# H1AR20.net
KiCad netlist of a schematic drawn in EAGLE
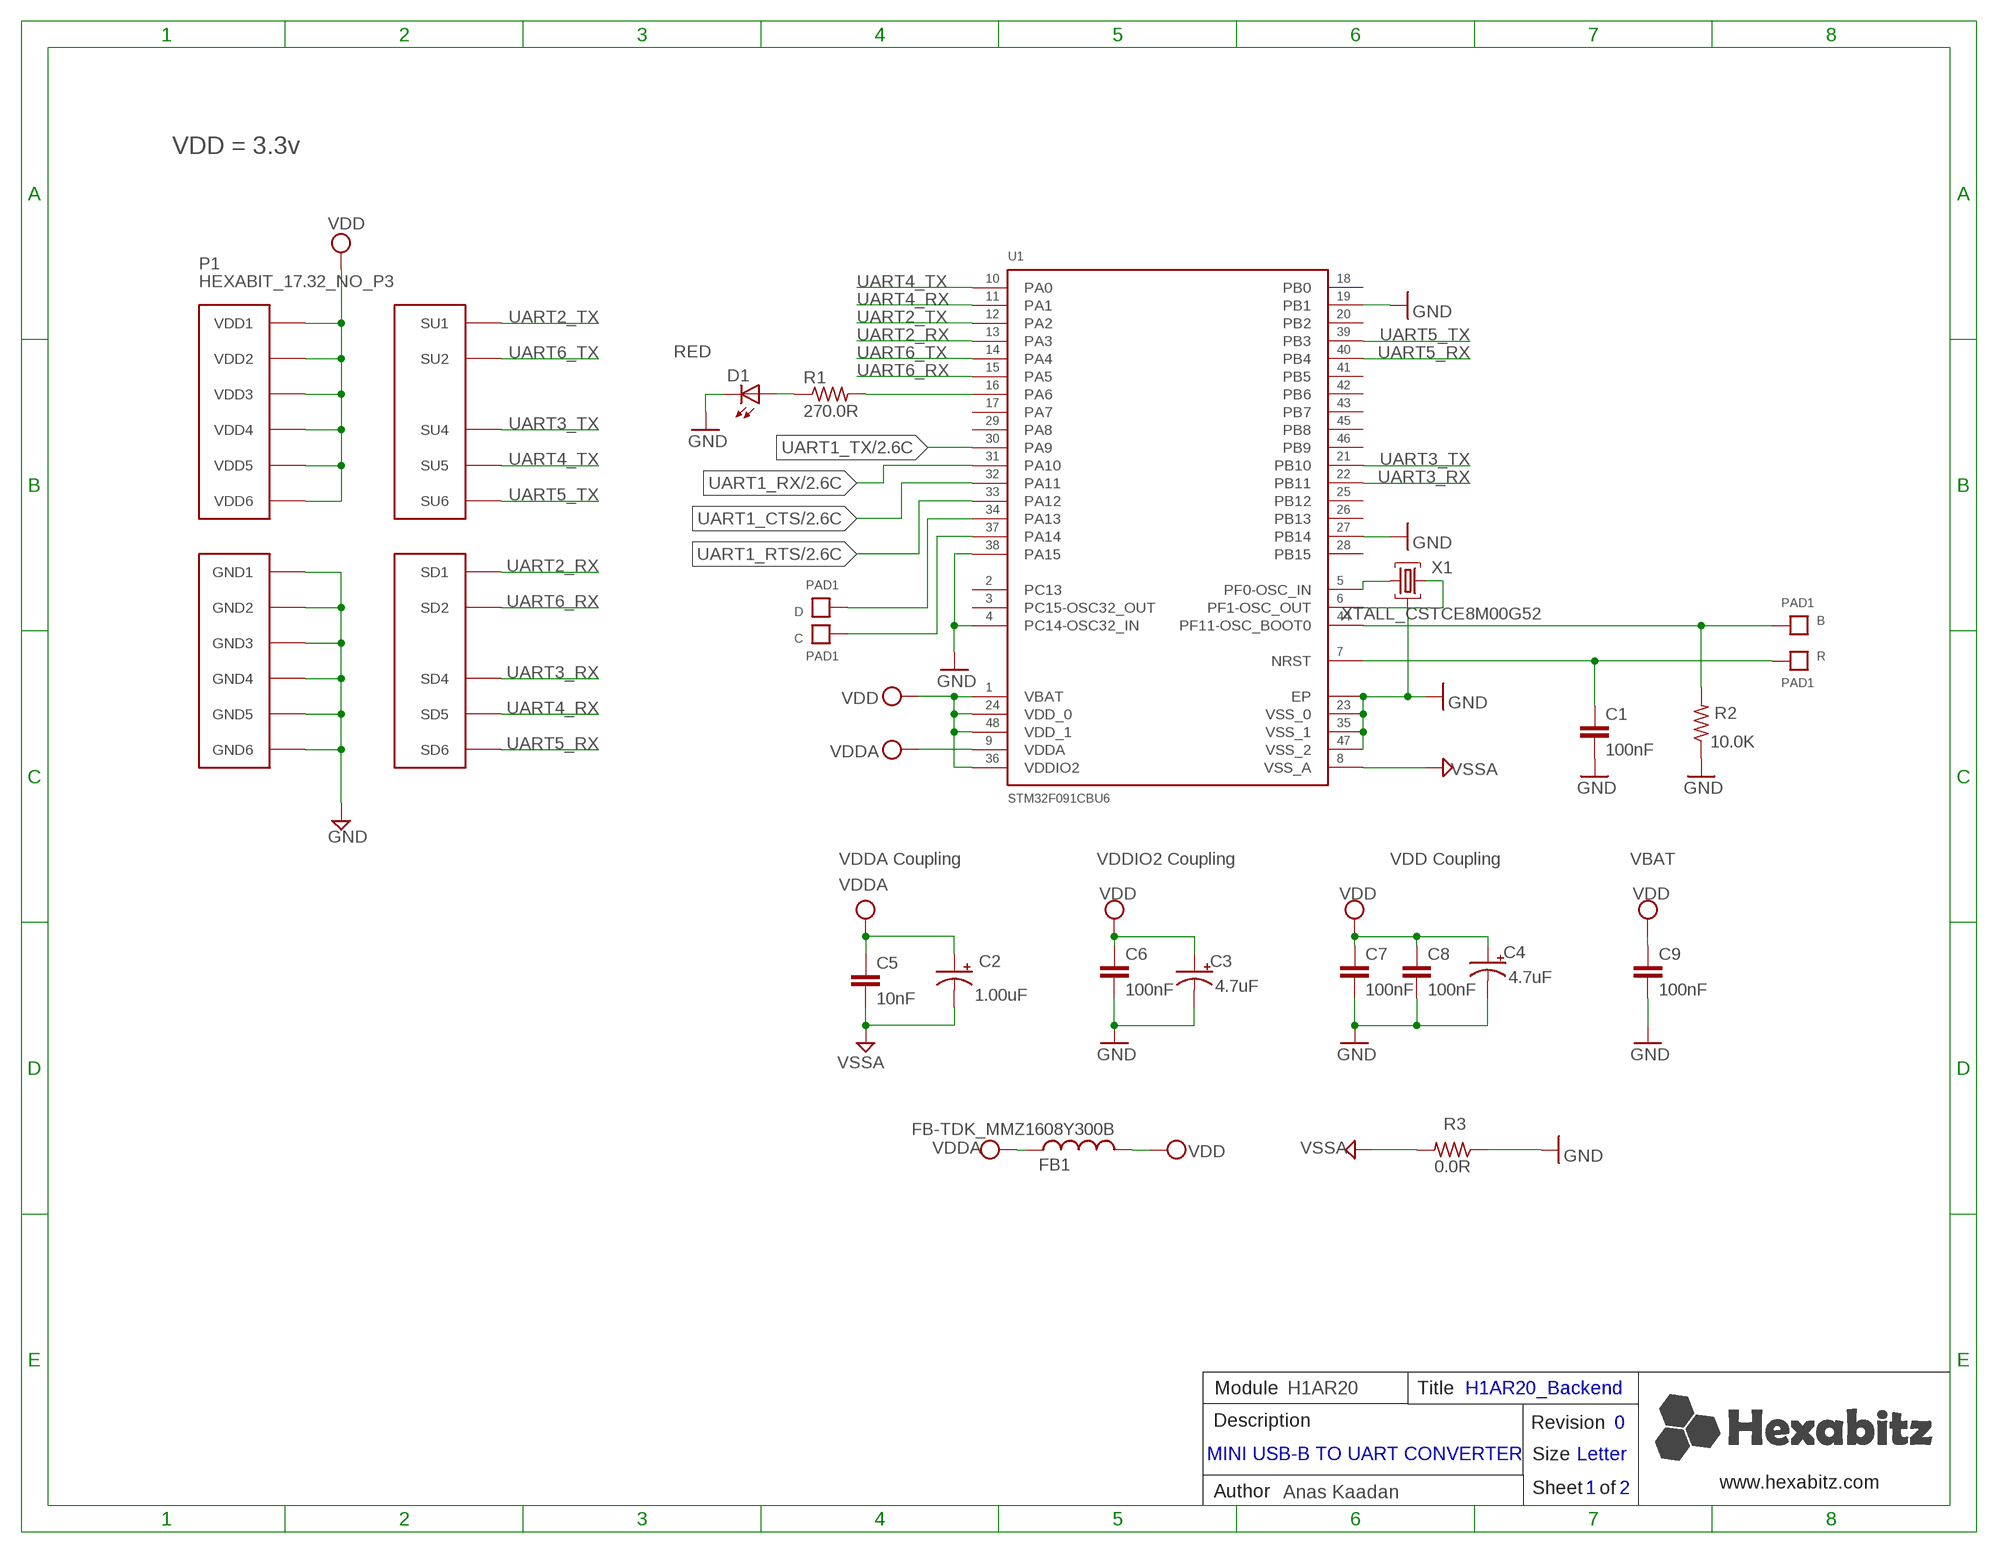
[diagram p0: schematic, sheet 1]
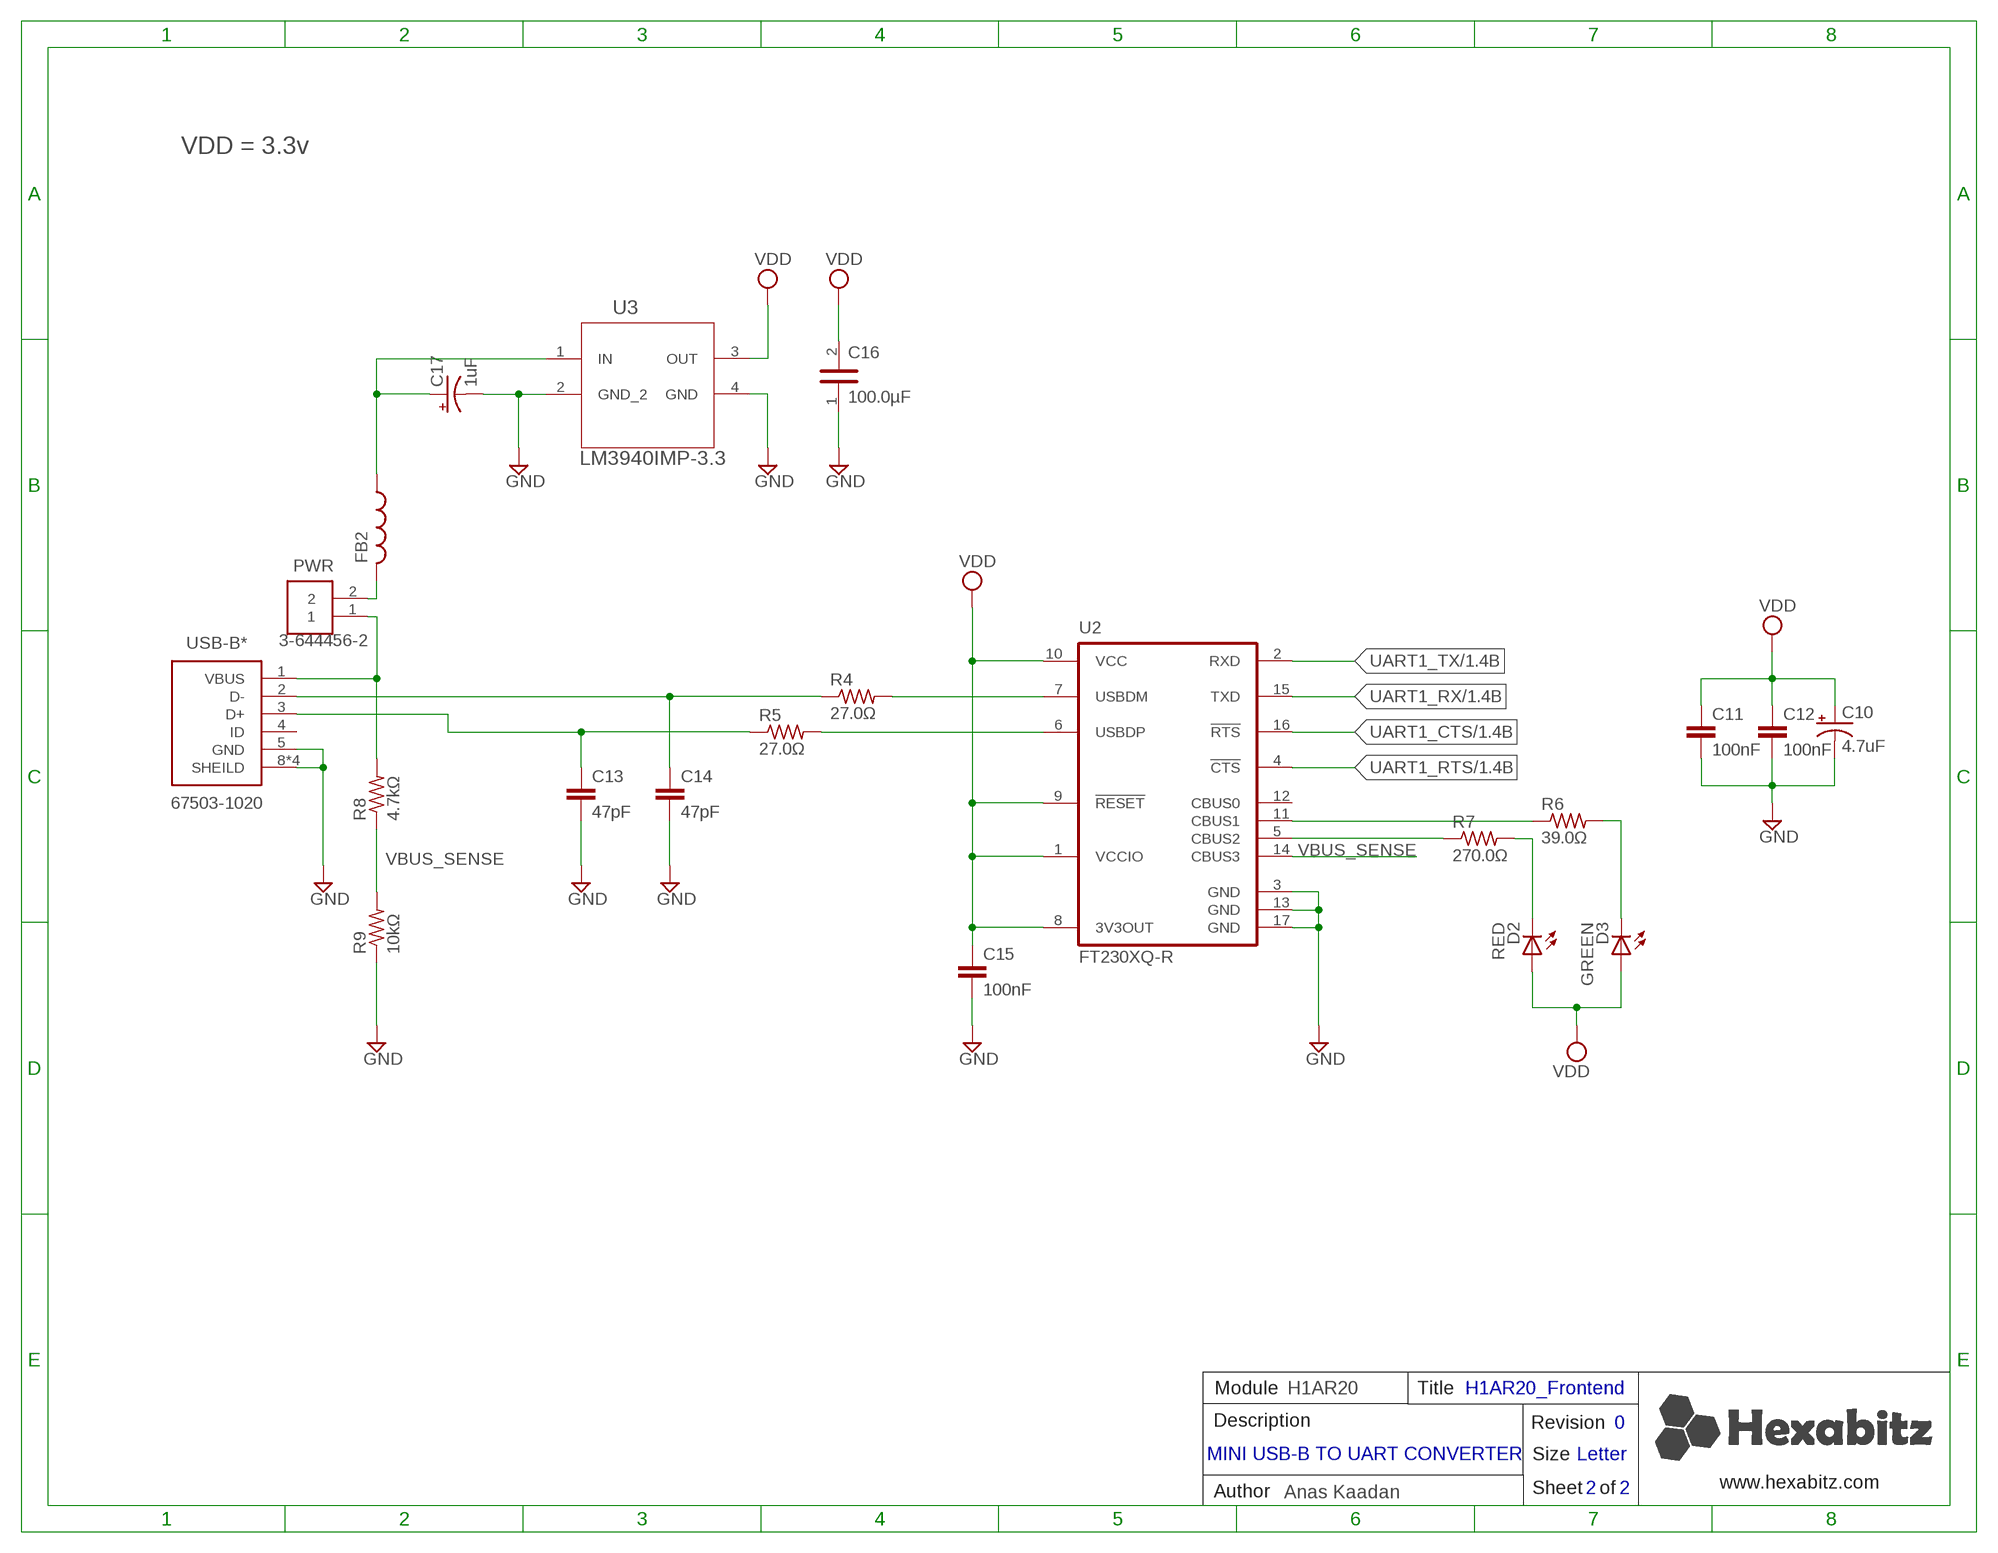
[diagram p1: schematic, sheet 2]

(export (version "E")
  (design (tool "Eeschema 10.0.6"))
  (components
    (comp (ref "B")
      (value "PAD1")
      (footprint "eagle-import:PAD1")
      (libsource (lib "eagle-import") (part "PAD1"))
    )
    (comp (ref "C")
      (value "PAD1")
      (footprint "eagle-import:PAD1")
      (libsource (lib "eagle-import") (part "PAD1"))
    )
    (comp (ref "C1")
      (value "100nF")
      (footprint "eagle-import:C-0603")
      (fields
        (field (name "CAPACITANCE") "100nF")
        (field (name "MFN") "KEMET")
        (field (name "MPN") "C0603C104K8RACTU")
        (field (name "OCTOPART_URL") "https://octopart.com/c0603c104k8ractu-kemet-145075?r=sp&s=9bS9ASSwSEqMCE9KBEQZ0g")
        (field (name "TOLERANCE") "10%")
        (field (name "VOLTAGE_RATING") "10V")
      )
      (libsource (lib "eagle-import") (part "C-0603"))
    )
    (comp (ref "C2")
      (value "1.00uF")
      (footprint "eagle-import:C-0805-POL")
      (fields
        (field (name "CAPACITANCE") "1.00uF")
        (field (name "MFN") "Yageo")
        (field (name "MPN") "CC0805KKX7R7BB105")
        (field (name "OCTOPART_URL") "https://octopart.com/cc0805kkx7r7bb105-yageo-8376555?r=sp&s=YKl1wwtkROau_X5nniH2ig")
        (field (name "TOLERANCE") "10%")
        (field (name "VOLTAGE_RATING") "16V")
      )
      (libsource (lib "eagle-import") (part "C-0805-POL"))
    )
    (comp (ref "C3")
      (value "4.7uF")
      (footprint "eagle-import:C-0805-POL")
      (fields
        (field (name "CAPACITANCE") "4.7uF")
        (field (name "MFN") "Murata")
        (field (name "MPN") "GRM21BC81E475KA12L")
        (field (name "OCTOPART_URL") "https://octopart.com/grm21bc81e475ka12l-murata-10331911?r=sp&s=RY3qZSD8T6mG6TC9CHI5qQ")
        (field (name "TOLERANCE") "10%")
        (field (name "VOLTAGE_RATING") "25V")
      )
      (libsource (lib "eagle-import") (part "C-0805-POL"))
    )
    (comp (ref "C4")
      (value "4.7uF")
      (footprint "eagle-import:C-0805-POL")
      (fields
        (field (name "CAPACITANCE") "4.7uF")
        (field (name "MFN") "Murata")
        (field (name "MPN") "GRM21BC81E475KA12L")
        (field (name "OCTOPART_URL") "https://octopart.com/grm21bc81e475ka12l-murata-10331911?r=sp&s=RY3qZSD8T6mG6TC9CHI5qQ")
        (field (name "TOLERANCE") "10%")
        (field (name "VOLTAGE_RATING") "25V")
      )
      (libsource (lib "eagle-import") (part "C-0805-POL"))
    )
    (comp (ref "C5")
      (value "10nF")
      (footprint "eagle-import:C-0603")
      (fields
        (field (name "CAPACITANCE") "10nF")
        (field (name "MFN") "KEMET")
        (field (name "MPN") "C0603C103K5RACTU")
        (field (name "OCTOPART_URL") "https://octopart.com/c0603c103k5ractu-kemet-133094?r=sp&s=R_iPBxLnSmGqhkU2rIMFpg")
        (field (name "TOLERANCE") "10%")
        (field (name "VOLTAGE_RATING") "50V")
      )
      (libsource (lib "eagle-import") (part "C-0603"))
    )
    (comp (ref "C6")
      (value "100nF")
      (footprint "eagle-import:C-0603")
      (fields
        (field (name "CAPACITANCE") "100nF")
        (field (name "MFN") "KEMET")
        (field (name "MPN") "C0603C104K8RACTU")
        (field (name "OCTOPART_URL") "https://octopart.com/c0603c104k8ractu-kemet-145075?r=sp&s=9bS9ASSwSEqMCE9KBEQZ0g")
        (field (name "TOLERANCE") "10%")
        (field (name "VOLTAGE_RATING") "10V")
      )
      (libsource (lib "eagle-import") (part "C-0603"))
    )
    (comp (ref "C7")
      (value "100nF")
      (footprint "eagle-import:C-0603")
      (fields
        (field (name "CAPACITANCE") "100nF")
        (field (name "MFN") "KEMET")
        (field (name "MPN") "C0603C104K8RACTU")
        (field (name "OCTOPART_URL") "https://octopart.com/c0603c104k8ractu-kemet-145075?r=sp&s=9bS9ASSwSEqMCE9KBEQZ0g")
        (field (name "TOLERANCE") "10%")
        (field (name "VOLTAGE_RATING") "10")
      )
      (libsource (lib "eagle-import") (part "C-0603"))
    )
    (comp (ref "C8")
      (value "100nF")
      (footprint "eagle-import:C-0603")
      (fields
        (field (name "CAPACITANCE") "100nF")
        (field (name "MFN") "KEMET")
        (field (name "MPN") "C0603C104K8RACTU")
        (field (name "OCTOPART_URL") "https://octopart.com/c0603c104k8ractu-kemet-145075?r=sp&s=9bS9ASSwSEqMCE9KBEQZ0g")
        (field (name "TOLERANCE") "10%")
        (field (name "VOLTAGE_RATING") "10V")
      )
      (libsource (lib "eagle-import") (part "C-0603"))
    )
    (comp (ref "C9")
      (value "100nF")
      (footprint "eagle-import:C-0603")
      (fields
        (field (name "CAPACITANCE") "100nF")
        (field (name "MFN") "KEMET")
        (field (name "MPN") "C0603C104K8RACTU")
        (field (name "OCTOPART_URL") "https://octopart.com/c0603c104k8ractu-kemet-145075?r=sp&s=9bS9ASSwSEqMCE9KBEQZ0g")
        (field (name "TOLERANCE") "10V")
        (field (name "VOLTAGE_RATING") "10%")
      )
      (libsource (lib "eagle-import") (part "C-0603"))
    )
    (comp (ref "D")
      (value "PAD1")
      (footprint "eagle-import:PAD1")
      (libsource (lib "eagle-import") (part "PAD1"))
    )
    (comp (ref "D1")
      (value "RED")
      (footprint "eagle-import:VLMS1300-GS08")
      (fields
        (field (name "MPN") "VLMS1300-GS08")
        (field (name "MFN") "Vishay")
        (field (name "MPN_1") "VLMS1300-GS08")
        (field (name "OCTOPART_URL") "https://octopart.com/vlms1300-gs08-vishay-21709201?r=sp&s=_gcP4_q8T1SC6PJQPTQ9yA")
      )
      (libsource (lib "eagle-import") (part "VLMS1300-GS08"))
    )
    (comp (ref "FB1")
      (value "FB-TDK_MMZ1608Y300B")
      (footprint "eagle-import:FB-TDK_MMZ1608Y300B")
      (fields
        (field (name "MFN") "TDK ")
        (field (name "MPN") "MMZ1608Y300B")
        (field (name "OCTOPART_URL") "https://octopart.com/mmz1608y300b-tdk-368280?r=sp&s=cd9_2ZEqQ9q9UNBuQgHAiA")
      )
      (libsource (lib "eagle-import") (part "FB-TDK_MMZ1608Y300B"))
    )
    (comp (ref "P1")
      (value "HEXABIT_17.32_NO_P3")
      (footprint "eagle-import:HEXABIT_17.32_NO_P3")
      (libsource (lib "eagle-import") (part "HEXABIT_?_NO_P317.32"))
    )
    (comp (ref "R")
      (value "PAD1")
      (footprint "eagle-import:PAD1")
      (libsource (lib "eagle-import") (part "PAD1"))
    )
    (comp (ref "R1")
      (value "270.0R")
      (footprint "eagle-import:R-0603")
      (fields
        (field (name "MFN") "Yageo")
        (field (name "MPN") "RC0603FR-07270RL")
        (field (name "OCTOPART_URL") "https://octopart.com/search?q=RC0603FR-07270RL&start=0")
        (field (name "RESISTANCE") "270.0 Ohm")
        (field (name "TOLERANCE") "1%")
      )
      (libsource (lib "eagle-import") (part "R-0603"))
    )
    (comp (ref "R2")
      (value "10.0K")
      (footprint "eagle-import:R-0603")
      (fields
        (field (name "MFN") "Vishay")
        (field (name "MPN") "CRCW060310K0JNEB")
        (field (name "OCTOPART_URL") "https://octopart.com/crcw060310k0jneb-vishay+dale-46603268")
        (field (name "RESISTANCE") "10.0K Ohm")
        (field (name "TOLERANCE") "5%")
      )
      (libsource (lib "eagle-import") (part "R-0603"))
    )
    (comp (ref "R3")
      (value "0.0R")
      (footprint "eagle-import:R-0603")
      (fields
        (field (name "MFN") "Yageo")
        (field (name "MPN") "RC0603JR-070RL")
        (field (name "OCTOPART_URL") "https://octopart.com/rc0603jr-070rl-yageo-1241539?r=sp&s=X2NteqRjRNWrnx42Y0aliA")
        (field (name "RESISTANCE") "0.0 Ohm")
      )
      (libsource (lib "eagle-import") (part "R-0603"))
    )
    (comp (ref "U1")
      (value "STM32F091CBU6")
      (footprint "eagle-import:STM32F091CBU6")
      (libsource (lib "eagle-import") (part "STM32F091CBU6"))
    )
    (comp (ref "X1")
      (value "XTALL_CSTCE8M00G52")
      (footprint "eagle-import:XTALL_CSTCE8M00G52")
      (fields (field (name "MPN") "CSTCE8M00G52Z-R0"))
      (libsource (lib "eagle-import") (part "XTALL_CSTCE8M00G52"))
    )
    (comp (ref "C10")
      (value "4.7uF")
      (footprint "eagle-import:C-0805-POL")
      (fields
        (field (name "CAPACITANCE") "4.7 µF")
        (field (name "MFN") "Panasonic")
        (field (name "MPN") "10TPU4R7MSI")
        (field (name "OCTOPART_URL") "https://octopart.com/10tpu4r7msi-panasonic-29487748")
        (field (name "TOLERANCE") "±20%")
        (field (name "VOLTAGE_RATING") "10.0 V")
      )
      (libsource (lib "eagle-import") (part "C-0805-POL"))
    )
    (comp (ref "C11")
      (value "100nF")
      (footprint "eagle-import:C-0603")
      (fields
        (field (name "CAPACITANCE") "100 nF")
        (field (name "MFN") "AVX")
        (field (name "MPN") "0603YC104K4T2A")
        (field (name "OCTOPART_URL") "https://octopart.com/0603yc104k4t2a-avx+interconnect+%2F+elco-8120651")
        (field (name "TOLERANCE") "±10%")
        (field (name "VOLTAGE_RATING") "16.0 V")
      )
      (libsource (lib "eagle-import") (part "C-0603"))
    )
    (comp (ref "C12")
      (value "100nF")
      (footprint "eagle-import:C-0603")
      (fields
        (field (name "CAPACITANCE") "100 nF")
        (field (name "MFN") "AVX")
        (field (name "MPN") "0603YC104K4T2A")
        (field (name "OCTOPART_URL") "https://octopart.com/0603yc104k4t2a-avx+interconnect+%2F+elco-8120651")
        (field (name "TOLERANCE") "±10%")
        (field (name "VOLTAGE_RATING") "16.0 V")
      )
      (libsource (lib "eagle-import") (part "C-0603"))
    )
    (comp (ref "C13")
      (value "47pF")
      (footprint "eagle-import:C-0603")
      (fields
        (field (name "CAPACITANCE") "47 pF")
        (field (name "MFN") "AVX")
        (field (name "MPN") "06035A470JAT2A")
        (field (name "OCTOPART_URL") "https://octopart.com/c3225x5r0j107m250ac-tdk-25947844?r=spc#")
        (field (name "TOLERANCE") "±5%")
        (field (name "VOLTAGE_RATING") "50.0 V")
      )
      (libsource (lib "eagle-import") (part "C-0603"))
    )
    (comp (ref "C14")
      (value "47pF")
      (footprint "eagle-import:C-0603")
      (fields
        (field (name "CAPACITANCE") "47 pF")
        (field (name "MFN") "AVX")
        (field (name "MPN") "06035A470JAT2A")
        (field (name "OCTOPART_URL") "https://octopart.com/06035a470jat2a-avx+interconnect+%2F+elco-46507018")
        (field (name "TOLERANCE") "±5%")
        (field (name "VOLTAGE_RATING") "50.0 V")
      )
      (libsource (lib "eagle-import") (part "C-0603"))
    )
    (comp (ref "C15")
      (value "100nF")
      (footprint "eagle-import:C-0603")
      (fields
        (field (name "CAPACITANCE") "100 nF")
        (field (name "MFN") "AVX")
        (field (name "MPN") "0603YC104K4T2A")
        (field (name "OCTOPART_URL") "https://octopart.com/0603yc104k4t2a-avx+interconnect+%2F+elco-8120651")
        (field (name "TOLERANCE") "±10%")
        (field (name "VOLTAGE_RATING") "16.0 V")
      )
      (libsource (lib "eagle-import") (part "C-0603"))
    )
    (comp (ref "C16")
      (value "100uF")
      (footprint "eagle-import:C-3225")
      (fields
        (field (name "CAPACITANCE") "100.0µF")
        (field (name "MPN") "C3225X5R0J107M250AC")
        (field (name "VOLTAGE") "6.3V")
      )
      (libsource (lib "eagle-import") (part "C-3225TDK_C3225X5R0J107M250AC_0_0"))
    )
    (comp (ref "C17")
      (value "1uF")
      (footprint "eagle-import:C-0805-POL")
      (fields
        (field (name "CAPACITANCE") "1.00 µF")
        (field (name "MFN") "AVX")
        (field (name "MPN") "TAJR105M016RNJ")
        (field (name "OCTOPART_URL") "http://octopart.com/tajr105m016rnj-avx-1188552")
        (field (name "TOLERANCE") "±20%")
        (field (name "VOLTAGE_RATING") "16.0 V")
      )
      (libsource (lib "eagle-import") (part "C-0805-POL"))
    )
    (comp (ref "D2")
      (value "RED")
      (footprint "eagle-import:VLMS1300-GS08")
      (fields (field (name "MPN") "VLMS1300-GS08"))
      (libsource (lib "eagle-import") (part "VLMS1300-GS08"))
    )
    (comp (ref "D3")
      (value "GREEN")
      (footprint "eagle-import:VLMS1300-GS08")
      (fields (field (name "MPN") "VLMTG1300-GS08"))
      (libsource (lib "eagle-import") (part "VLMTG1300-GS08"))
    )
    (comp (ref "FB2")
      (value "FB-TDK_MMZ1608Y300B")
      (footprint "eagle-import:FB-TDK_MMZ1608Y300B")
      (fields
        (field (name "MFN") "TDK")
        (field (name "MPN") "MMZ1608Y300B")
        (field (name "OCTOPART_URL") "https://octopart.com/mmz1608y300b-tdk-368280")
      )
      (libsource (lib "eagle-import") (part "FB-TDK_MMZ1608Y300B"))
    )
    (comp (ref "PWR")
      (value "3-644456-2")
      (footprint "eagle-import:TE_3-644456-2")
      (fields (field (name "MF") "TE Connectivity"))
      (libsource (lib "eagle-import") (part "3-644456-2"))
    )
    (comp (ref "R4")
      (value "27.0Ω")
      (footprint "eagle-import:R-0603")
      (fields
        (field (name "MFN") "Vishay")
        (field (name "MPN") "CRCW060327R0FKEA")
        (field (name "OCTOPART_URL") "https://octopart.com/crcw060327r0fkea-vishay-39833156")
        (field (name "RESISTANCE") "27.0 Ω")
        (field (name "TOLERANCE") "±1%")
      )
      (libsource (lib "eagle-import") (part "R-0603"))
    )
    (comp (ref "R5")
      (value "27.0Ω")
      (footprint "eagle-import:R-0603")
      (fields
        (field (name "MFN") "Vishay")
        (field (name "MPN") "CRCW060327R0FKEA")
        (field (name "OCTOPART_URL") "https://octopart.com/crcw060327r0fkea-vishay-39833156")
        (field (name "RESISTANCE") "27.0 Ω")
        (field (name "TOLERANCE") "±1%")
      )
      (libsource (lib "eagle-import") (part "R-0603"))
    )
    (comp (ref "R6")
      (value "39.0Ω")
      (footprint "eagle-import:R-0603")
      (fields
        (field (name "MFN") "Panasonic")
        (field (name "MPN") "ERJ-3GEYJ390V")
        (field (name "OCTOPART_URL") "https://octopart.com/erj-3geyj390v-panasonic-55422095")
        (field (name "RESISTANCE") "39.0 Ω")
        (field (name "TOLERANCE") "±5%")
      )
      (libsource (lib "eagle-import") (part "R-0603"))
    )
    (comp (ref "R7")
      (value "270.0Ω")
      (footprint "eagle-import:R-0603")
      (fields
        (field (name "MFN") "Panasonic")
        (field (name "MPN") "ERJ-3GEYJ271V")
        (field (name "OCTOPART_URL") "https://octopart.com/erj-3geyj271v-panasonic-55560546")
        (field (name "RESISTANCE") "270.0 Ω")
        (field (name "TOLERANCE") "±5%")
      )
      (libsource (lib "eagle-import") (part "R-0603"))
    )
    (comp (ref "R8")
      (value "4.7kΩ")
      (footprint "eagle-import:R-0603")
      (fields
        (field (name "MFN") "Vishay")
        (field (name "MPN") "CRCW06034K70FKEA")
        (field (name "OCTOPART_URL") "http://octopart.com/crcw06034k70fkea-vishay-39455708")
        (field (name "RESISTANCE") "4.7 kΩ")
        (field (name "TOLERANCE") "±1%")
      )
      (libsource (lib "eagle-import") (part "R-0603"))
    )
    (comp (ref "R9")
      (value "10kΩ")
      (footprint "eagle-import:R-0603")
      (fields
        (field (name "MFN") "Vishay")
        (field (name "MPN") "CRCW060310K0JNEB")
        (field (name "OCTOPART_URL") "https://octopart.com/crcw060310k0jneb-vishay+dale-46603268")
        (field (name "RESISTANCE") "10.0 kΩ")
        (field (name "TOLERANCE") "±5%")
      )
      (libsource (lib "eagle-import") (part "R-0603"))
    )
    (comp (ref "U2")
      (value "FT230XQ-R")
      (footprint "eagle-import:QFN16")
      (libsource (lib "eagle-import") (part "FT230XQ-R"))
    )
    (comp (ref "U3")
      (value "LM3940IMP-3.3")
      (footprint "eagle-import:SOT230P696X180-4N")
      (fields (field (name "MPN") "LM3940IMP-3.3/NOPB"))
      (libsource (lib "eagle-import") (part "LM3940IMP-3.3"))
    )
    (comp (ref "USB-B*")
      (value "67503-1020")
      (footprint "eagle-import:67503-1020")
      (libsource (lib "eagle-import") (part "67503-1020"))
    )
  )
  (nets
    (net (code "1") (name "GND") (class "Default")
      (node (ref "C1") (pin "2") (pinfunction "2_2") (pintype "passive"))
      (node (ref "C10") (pin "2") (pinfunction "-_2") (pintype "passive"))
      (node (ref "C11") (pin "2") (pinfunction "2_2") (pintype "passive"))
      (node (ref "C12") (pin "2") (pinfunction "2_2") (pintype "passive"))
      (node (ref "C13") (pin "2") (pinfunction "2_2") (pintype "passive"))
      (node (ref "C14") (pin "2") (pinfunction "2_2") (pintype "passive"))
      (node (ref "C15") (pin "2") (pinfunction "2_2") (pintype "passive"))
      (node (ref "C16") (pin "1") (pinfunction "1_1") (pintype "bidirectional"))
      (node (ref "C17") (pin "2") (pinfunction "-_2") (pintype "passive"))
      (node (ref "C3") (pin "2") (pinfunction "-_2") (pintype "passive"))
      (node (ref "C4") (pin "2") (pinfunction "-_2") (pintype "passive"))
      (node (ref "C6") (pin "2") (pinfunction "2_2") (pintype "passive"))
      (node (ref "C7") (pin "2") (pinfunction "2_2") (pintype "passive"))
      (node (ref "C8") (pin "2") (pinfunction "2_2") (pintype "passive"))
      (node (ref "C9") (pin "2") (pinfunction "2_2") (pintype "passive"))
      (node (ref "D1") (pin "C") (pinfunction "C_C") (pintype "passive"))
      (node (ref "P1") (pin "PAD_PD10") (pinfunction "GND4_PAD_PD10") (pintype "power_in"))
      (node (ref "P1") (pin "PAD_PD11") (pinfunction "GND5_PAD_PD11") (pintype "power_in"))
      (node (ref "P1") (pin "PAD_PD12") (pinfunction "GND6_PAD_PD12") (pintype "power_in"))
      (node (ref "P1") (pin "PAD_PD7") (pinfunction "GND1_PAD_PD7") (pintype "power_in"))
      (node (ref "P1") (pin "PAD_PD8") (pinfunction "GND2_PAD_PD8") (pintype "power_in"))
      (node (ref "P1") (pin "PAD_PD9") (pinfunction "GND3_PAD_PD9") (pintype "power_in"))
      (node (ref "R2") (pin "1") (pinfunction "1_1") (pintype "passive"))
      (node (ref "R3") (pin "1") (pinfunction "1_1") (pintype "passive"))
      (node (ref "R9") (pin "1") (pinfunction "1_1") (pintype "passive"))
      (node (ref "U1") (pin "EP") (pinfunction "EP_EP") (pintype "power_in"))
      (node (ref "U1") (pin "P$19") (pinfunction "PB1_P$19") (pintype "bidirectional"))
      (node (ref "U1") (pin "P$23") (pinfunction "VSS_0_P$23") (pintype "power_in"))
      (node (ref "U1") (pin "P$27") (pinfunction "PB14_P$27") (pintype "bidirectional"))
      (node (ref "U1") (pin "P$3") (pinfunction "PC14-OSC32_IN_P$3") (pintype "bidirectional"))
      (node (ref "U1") (pin "P$35") (pinfunction "VSS_1_P$35") (pintype "power_in"))
      (node (ref "U1") (pin "P$38") (pinfunction "PA15_P$38") (pintype "bidirectional"))
      (node (ref "U1") (pin "P$47") (pinfunction "VSS_2_P$47") (pintype "power_in"))
      (node (ref "U2") (pin "13") (pinfunction "GND_13") (pintype "power_in"))
      (node (ref "U2") (pin "17") (pinfunction "GND_17") (pintype "power_in"))
      (node (ref "U2") (pin "3") (pinfunction "GND_3") (pintype "power_in"))
      (node (ref "U3") (pin "2") (pinfunction "GND_2_2") (pintype "passive"))
      (node (ref "U3") (pin "4") (pinfunction "GND_4") (pintype "passive"))
      (node (ref "USB-B*") (pin "10") (pinfunction "SHEILD_10") (pintype "passive"))
      (node (ref "USB-B*") (pin "11") (pinfunction "SHEILD_11") (pintype "passive"))
      (node (ref "USB-B*") (pin "5") (pinfunction "GND_5") (pintype "passive"))
      (node (ref "USB-B*") (pin "8") (pinfunction "SHEILD_8") (pintype "passive"))
      (node (ref "USB-B*") (pin "9") (pinfunction "SHEILD_9") (pintype "passive"))
      (node (ref "X1") (pin "P$2") (pinfunction "2_P$2") (pintype "passive"))
    )
    (net (code "2") (name "Net-(C17-+)") (class "Default")
      (node (ref "C17") (pin "1") (pinfunction "+_1") (pintype "passive"))
      (node (ref "FB2") (pin "1") (pinfunction "1_1") (pintype "passive"))
      (node (ref "U3") (pin "1") (pinfunction "IN_1") (pintype "power_in"))
    )
    (net (code "3") (name "Net-(D1-PadA)") (class "Default")
      (node (ref "D1") (pin "A") (pinfunction "A_A") (pintype "passive"))
      (node (ref "R1") (pin "1") (pinfunction "1_1") (pintype "passive"))
    )
    (net (code "4") (name "Net-(D2-PadC)") (class "Default")
      (node (ref "D2") (pin "C") (pinfunction "C_C") (pintype "passive"))
      (node (ref "R7") (pin "2") (pinfunction "2_2") (pintype "passive"))
    )
    (net (code "5") (name "Net-(D3-PadC)") (class "Default")
      (node (ref "D3") (pin "C") (pinfunction "C_C") (pintype "passive"))
      (node (ref "R6") (pin "2") (pinfunction "2_2") (pintype "passive"))
    )
    (net (code "6") (name "Net-(FB2-Pad2)") (class "Default")
      (node (ref "FB2") (pin "2") (pinfunction "2_2") (pintype "passive"))
      (node (ref "PWR") (pin "2") (pinfunction "2_2") (pintype "passive"))
    )
    (net (code "7") (name "Net-(U1-NRST)") (class "Default")
      (node (ref "C1") (pin "1") (pinfunction "1_1") (pintype "passive"))
      (node (ref "R") (pin "P$1") (pinfunction "P$1_P$1") (pintype "passive"))
      (node (ref "R") (pin "P$2") (pinfunction "P$1_P$2") (pintype "passive"))
      (node (ref "U1") (pin "P$7") (pinfunction "NRST_P$7") (pintype "passive"))
    )
    (net (code "8") (name "Net-(U1-PA6)") (class "Default")
      (node (ref "R1") (pin "2") (pinfunction "2_2") (pintype "passive"))
      (node (ref "U1") (pin "P$16") (pinfunction "PA6_P$16") (pintype "bidirectional"))
    )
    (net (code "9") (name "Net-(U1-PA13)") (class "Default")
      (node (ref "D") (pin "P$1") (pinfunction "P$1_P$1") (pintype "passive"))
      (node (ref "D") (pin "P$2") (pinfunction "P$1_P$2") (pintype "passive"))
      (node (ref "U1") (pin "P$34") (pinfunction "PA13_P$34") (pintype "bidirectional"))
    )
    (net (code "10") (name "Net-(U1-PA14)") (class "Default")
      (node (ref "C") (pin "P$1") (pinfunction "P$1_P$1") (pintype "passive"))
      (node (ref "C") (pin "P$2") (pinfunction "P$1_P$2") (pintype "passive"))
      (node (ref "U1") (pin "P$37") (pinfunction "PA14_P$37") (pintype "bidirectional"))
    )
    (net (code "11") (name "Net-(U1-PF0-OSC_IN)") (class "Default")
      (node (ref "U1") (pin "P$5") (pinfunction "PF0-OSC_IN_P$5") (pintype "bidirectional"))
      (node (ref "X1") (pin "P$1") (pinfunction "1_P$1") (pintype "passive"))
    )
    (net (code "12") (name "Net-(U1-PF1-OSC_OUT)") (class "Default")
      (node (ref "U1") (pin "P$6") (pinfunction "PF1-OSC_OUT_P$6") (pintype "bidirectional"))
      (node (ref "X1") (pin "P$3") (pinfunction "3_P$3") (pintype "passive"))
    )
    (net (code "13") (name "Net-(U1-PF11-OSC_BOOT0)") (class "Default")
      (node (ref "B") (pin "P$1") (pinfunction "P$1_P$1") (pintype "passive"))
      (node (ref "B") (pin "P$2") (pinfunction "P$1_P$2") (pintype "passive"))
      (node (ref "R2") (pin "2") (pinfunction "2_2") (pintype "passive"))
      (node (ref "U1") (pin "P$44") (pinfunction "PF11-OSC_BOOT0_P$44") (pintype "bidirectional"))
    )
    (net (code "14") (name "Net-(U2-CBUS1)") (class "Default")
      (node (ref "R6") (pin "1") (pinfunction "1_1") (pintype "passive"))
      (node (ref "U2") (pin "11") (pinfunction "CBUS1_11") (pintype "bidirectional"))
    )
    (net (code "15") (name "Net-(U2-CBUS2)") (class "Default")
      (node (ref "R7") (pin "1") (pinfunction "1_1") (pintype "passive"))
      (node (ref "U2") (pin "5") (pinfunction "CBUS2_5") (pintype "bidirectional"))
    )
    (net (code "16") (name "Net-(U2-USBDM)") (class "Default")
      (node (ref "R4") (pin "2") (pinfunction "2_2") (pintype "passive"))
      (node (ref "U2") (pin "7") (pinfunction "USBDM_7") (pintype "bidirectional"))
    )
    (net (code "17") (name "Net-(U2-USBDP)") (class "Default")
      (node (ref "R5") (pin "2") (pinfunction "2_2") (pintype "passive"))
      (node (ref "U2") (pin "6") (pinfunction "USBDP_6") (pintype "bidirectional"))
    )
    (net (code "18") (name "Net-(USB-B*-D+)") (class "Default")
      (node (ref "C13") (pin "1") (pinfunction "1_1") (pintype "passive"))
      (node (ref "R5") (pin "1") (pinfunction "1_1") (pintype "passive"))
      (node (ref "USB-B*") (pin "3") (pinfunction "D+_3") (pintype "passive"))
    )
    (net (code "19") (name "Net-(USB-B*-D-)") (class "Default")
      (node (ref "C14") (pin "1") (pinfunction "1_1") (pintype "passive"))
      (node (ref "R4") (pin "1") (pinfunction "1_1") (pintype "passive"))
      (node (ref "USB-B*") (pin "2") (pinfunction "D-_2") (pintype "passive"))
    )
    (net (code "20") (name "Net-(USB-B*-VBUS)") (class "Default")
      (node (ref "PWR") (pin "1") (pinfunction "1_1") (pintype "passive"))
      (node (ref "R8") (pin "2") (pinfunction "2_2") (pintype "passive"))
      (node (ref "USB-B*") (pin "1") (pinfunction "VBUS_1") (pintype "passive"))
    )
    (net (code "21") (name "UART1_CTS") (class "Default")
      (node (ref "U1") (pin "P$32") (pinfunction "PA11_P$32") (pintype "bidirectional"))
      (node (ref "U2") (pin "16") (pinfunction "~{RTS}_16") (pintype "output"))
    )
    (net (code "22") (name "UART1_RTS") (class "Default")
      (node (ref "U1") (pin "P$33") (pinfunction "PA12_P$33") (pintype "bidirectional"))
      (node (ref "U2") (pin "4") (pinfunction "~{CTS}_4") (pintype "input"))
    )
    (net (code "23") (name "UART1_RX") (class "Default")
      (node (ref "U1") (pin "P$31") (pinfunction "PA10_P$31") (pintype "bidirectional"))
      (node (ref "U2") (pin "15") (pinfunction "TXD_15") (pintype "output"))
    )
    (net (code "24") (name "UART1_TX") (class "Default")
      (node (ref "U1") (pin "P$30") (pinfunction "PA9_P$30") (pintype "bidirectional"))
      (node (ref "U2") (pin "2") (pinfunction "RXD_2") (pintype "input"))
    )
    (net (code "25") (name "UART2_RX") (class "Default")
      (node (ref "P1") (pin "PAD_PD1") (pinfunction "SD1_PAD_PD1") (pintype "bidirectional"))
      (node (ref "U1") (pin "P$13") (pinfunction "PA3_P$13") (pintype "bidirectional"))
    )
    (net (code "26") (name "UART2_TX") (class "Default")
      (node (ref "P1") (pin "PAD_PU1") (pinfunction "SU1_PAD_PU1") (pintype "bidirectional"))
      (node (ref "U1") (pin "P$12") (pinfunction "PA2_P$12") (pintype "bidirectional"))
    )
    (net (code "27") (name "UART3_RX") (class "Default")
      (node (ref "P1") (pin "PAD_PD4") (pinfunction "SD4_PAD_PD4") (pintype "bidirectional"))
      (node (ref "U1") (pin "P$22") (pinfunction "PB11_P$22") (pintype "bidirectional"))
    )
    (net (code "28") (name "UART3_TX") (class "Default")
      (node (ref "P1") (pin "PAD_PU4") (pinfunction "SU4_PAD_PU4") (pintype "bidirectional"))
      (node (ref "U1") (pin "P$21") (pinfunction "PB10_P$21") (pintype "bidirectional"))
    )
    (net (code "29") (name "UART4_RX") (class "Default")
      (node (ref "P1") (pin "PAD_PD5") (pinfunction "SD5_PAD_PD5") (pintype "bidirectional"))
      (node (ref "U1") (pin "P$11") (pinfunction "PA1_P$11") (pintype "bidirectional"))
    )
    (net (code "30") (name "UART4_TX") (class "Default")
      (node (ref "P1") (pin "PAD_PU5") (pinfunction "SU5_PAD_PU5") (pintype "bidirectional"))
      (node (ref "U1") (pin "P$10") (pinfunction "PA0_P$10") (pintype "bidirectional"))
    )
    (net (code "31") (name "UART5_RX") (class "Default")
      (node (ref "P1") (pin "PAD_PD6") (pinfunction "SD6_PAD_PD6") (pintype "bidirectional"))
      (node (ref "U1") (pin "P$40") (pinfunction "PB4_P$40") (pintype "bidirectional"))
    )
    (net (code "32") (name "UART5_TX") (class "Default")
      (node (ref "P1") (pin "PAD_PU6") (pinfunction "SU6_PAD_PU6") (pintype "bidirectional"))
      (node (ref "U1") (pin "P$39") (pinfunction "PB3_P$39") (pintype "bidirectional"))
    )
    (net (code "33") (name "UART6_RX") (class "Default")
      (node (ref "P1") (pin "PAD_PD2") (pinfunction "SD2_PAD_PD2") (pintype "bidirectional"))
      (node (ref "U1") (pin "P$15") (pinfunction "PA5_P$15") (pintype "bidirectional"))
    )
    (net (code "34") (name "UART6_TX") (class "Default")
      (node (ref "P1") (pin "PAD_PU2") (pinfunction "SU2_PAD_PU2") (pintype "bidirectional"))
      (node (ref "U1") (pin "P$14") (pinfunction "PA4_P$14") (pintype "bidirectional"))
    )
    (net (code "35") (name "VBUS_SENSE") (class "Default")
      (node (ref "R8") (pin "1") (pinfunction "1_1") (pintype "passive"))
      (node (ref "R9") (pin "2") (pinfunction "2_2") (pintype "passive"))
      (node (ref "U2") (pin "14") (pinfunction "CBUS3_14") (pintype "bidirectional"))
    )
    (net (code "36") (name "VDD") (class "Default")
      (node (ref "C10") (pin "1") (pinfunction "+_1") (pintype "passive"))
      (node (ref "C11") (pin "1") (pinfunction "1_1") (pintype "passive"))
      (node (ref "C12") (pin "1") (pinfunction "1_1") (pintype "passive"))
      (node (ref "C15") (pin "1") (pinfunction "1_1") (pintype "passive"))
      (node (ref "C16") (pin "2") (pinfunction "2_2") (pintype "bidirectional"))
      (node (ref "C3") (pin "1") (pinfunction "+_1") (pintype "passive"))
      (node (ref "C4") (pin "1") (pinfunction "+_1") (pintype "passive"))
      (node (ref "C6") (pin "1") (pinfunction "1_1") (pintype "passive"))
      (node (ref "C7") (pin "1") (pinfunction "1_1") (pintype "passive"))
      (node (ref "C8") (pin "1") (pinfunction "1_1") (pintype "passive"))
      (node (ref "C9") (pin "1") (pinfunction "1_1") (pintype "passive"))
      (node (ref "D2") (pin "A") (pinfunction "A_A") (pintype "passive"))
      (node (ref "D3") (pin "A") (pinfunction "A_A") (pintype "passive"))
      (node (ref "FB1") (pin "2") (pinfunction "2_2") (pintype "passive"))
      (node (ref "P1") (pin "PAD_PU10") (pinfunction "VDD4_PAD_PU10") (pintype "power_in"))
      (node (ref "P1") (pin "PAD_PU11") (pinfunction "VDD5_PAD_PU11") (pintype "power_in"))
      (node (ref "P1") (pin "PAD_PU12") (pinfunction "VDD6_PAD_PU12") (pintype "power_in"))
      (node (ref "P1") (pin "PAD_PU7") (pinfunction "VDD1_PAD_PU7") (pintype "power_in"))
      (node (ref "P1") (pin "PAD_PU8") (pinfunction "VDD2_PAD_PU8") (pintype "power_in"))
      (node (ref "P1") (pin "PAD_PU9") (pinfunction "VDD3_PAD_PU9") (pintype "power_in"))
      (node (ref "U1") (pin "P$1") (pinfunction "VBAT_P$1") (pintype "power_in"))
      (node (ref "U1") (pin "P$24") (pinfunction "VDD_0_P$24") (pintype "power_in"))
      (node (ref "U1") (pin "P$36") (pinfunction "VDDIO2_P$36") (pintype "power_in"))
      (node (ref "U1") (pin "P$48") (pinfunction "VDD_1_P$48") (pintype "power_in"))
      (node (ref "U2") (pin "1") (pinfunction "VCCIO_1") (pintype "input"))
      (node (ref "U2") (pin "10") (pinfunction "VCC_10") (pintype "power_in"))
      (node (ref "U2") (pin "8") (pinfunction "3V3OUT_8") (pintype "passive"))
      (node (ref "U2") (pin "9") (pinfunction "~{RESET}_9") (pintype "input"))
      (node (ref "U3") (pin "3") (pinfunction "OUT_3") (pintype "output"))
    )
    (net (code "37") (name "VDDA") (class "Default")
      (node (ref "C2") (pin "1") (pinfunction "+_1") (pintype "passive"))
      (node (ref "C5") (pin "1") (pinfunction "1_1") (pintype "passive"))
      (node (ref "FB1") (pin "1") (pinfunction "1_1") (pintype "passive"))
      (node (ref "U1") (pin "P$9") (pinfunction "VDDA_P$9") (pintype "power_in"))
    )
    (net (code "38") (name "VSSA") (class "Default")
      (node (ref "C2") (pin "2") (pinfunction "-_2") (pintype "passive"))
      (node (ref "C5") (pin "2") (pinfunction "2_2") (pintype "passive"))
      (node (ref "R3") (pin "2") (pinfunction "2_2") (pintype "passive"))
      (node (ref "U1") (pin "P$8") (pinfunction "VSS_A_P$8") (pintype "power_in"))
    )
    (net (code "39") (name "unconnected-(U1-PA7-PadP$17)") (class "Default")
      (node (ref "U1") (pin "P$17") (pinfunction "PA7_P$17") (pintype "bidirectional"))
    )
    (net (code "40") (name "unconnected-(U1-PA8-PadP$29)") (class "Default")
      (node (ref "U1") (pin "P$29") (pinfunction "PA8_P$29") (pintype "bidirectional"))
    )
    (net (code "41") (name "unconnected-(U1-PB0-PadP$18)") (class "Default")
      (node (ref "U1") (pin "P$18") (pinfunction "PB0_P$18") (pintype "bidirectional"))
    )
    (net (code "42") (name "unconnected-(U1-PB2-PadP$20)") (class "Default")
      (node (ref "U1") (pin "P$20") (pinfunction "PB2_P$20") (pintype "bidirectional"))
    )
    (net (code "43") (name "unconnected-(U1-PB5-PadP$41)") (class "Default")
      (node (ref "U1") (pin "P$41") (pinfunction "PB5_P$41") (pintype "bidirectional"))
    )
    (net (code "44") (name "unconnected-(U1-PB6-PadP$42)") (class "Default")
      (node (ref "U1") (pin "P$42") (pinfunction "PB6_P$42") (pintype "bidirectional"))
    )
    (net (code "45") (name "unconnected-(U1-PB7-PadP$43)") (class "Default")
      (node (ref "U1") (pin "P$43") (pinfunction "PB7_P$43") (pintype "bidirectional"))
    )
    (net (code "46") (name "unconnected-(U1-PB8-PadP$45)") (class "Default")
      (node (ref "U1") (pin "P$45") (pinfunction "PB8_P$45") (pintype "bidirectional"))
    )
    (net (code "47") (name "unconnected-(U1-PB9-PadP$46)") (class "Default")
      (node (ref "U1") (pin "P$46") (pinfunction "PB9_P$46") (pintype "bidirectional"))
    )
    (net (code "48") (name "unconnected-(U1-PB12-PadP$25)") (class "Default")
      (node (ref "U1") (pin "P$25") (pinfunction "PB12_P$25") (pintype "bidirectional"))
    )
    (net (code "49") (name "unconnected-(U1-PB13-PadP$26)") (class "Default")
      (node (ref "U1") (pin "P$26") (pinfunction "PB13_P$26") (pintype "bidirectional"))
    )
    (net (code "50") (name "unconnected-(U1-PB15-PadP$28)") (class "Default")
      (node (ref "U1") (pin "P$28") (pinfunction "PB15_P$28") (pintype "bidirectional"))
    )
    (net (code "51") (name "unconnected-(U1-PC13-PadP$2)") (class "Default")
      (node (ref "U1") (pin "P$2") (pinfunction "PC13_P$2") (pintype "bidirectional"))
    )
    (net (code "52") (name "unconnected-(U1-PC15-OSC32_OUT-PadP$4)") (class "Default")
      (node (ref "U1") (pin "P$4") (pinfunction "PC15-OSC32_OUT_P$4") (pintype "bidirectional"))
    )
    (net (code "53") (name "unconnected-(U2-CBUS0-Pad12)") (class "Default")
      (node (ref "U2") (pin "12") (pinfunction "CBUS0_12") (pintype "bidirectional"))
    )
    (net (code "54") (name "unconnected-(USB-B*-ID-Pad4)") (class "Default")
      (node (ref "USB-B*") (pin "4") (pinfunction "ID_4") (pintype "passive"))
    )
  )
)
